# comfort_board.net
KiCad netlist of a schematic drawn in EAGLE
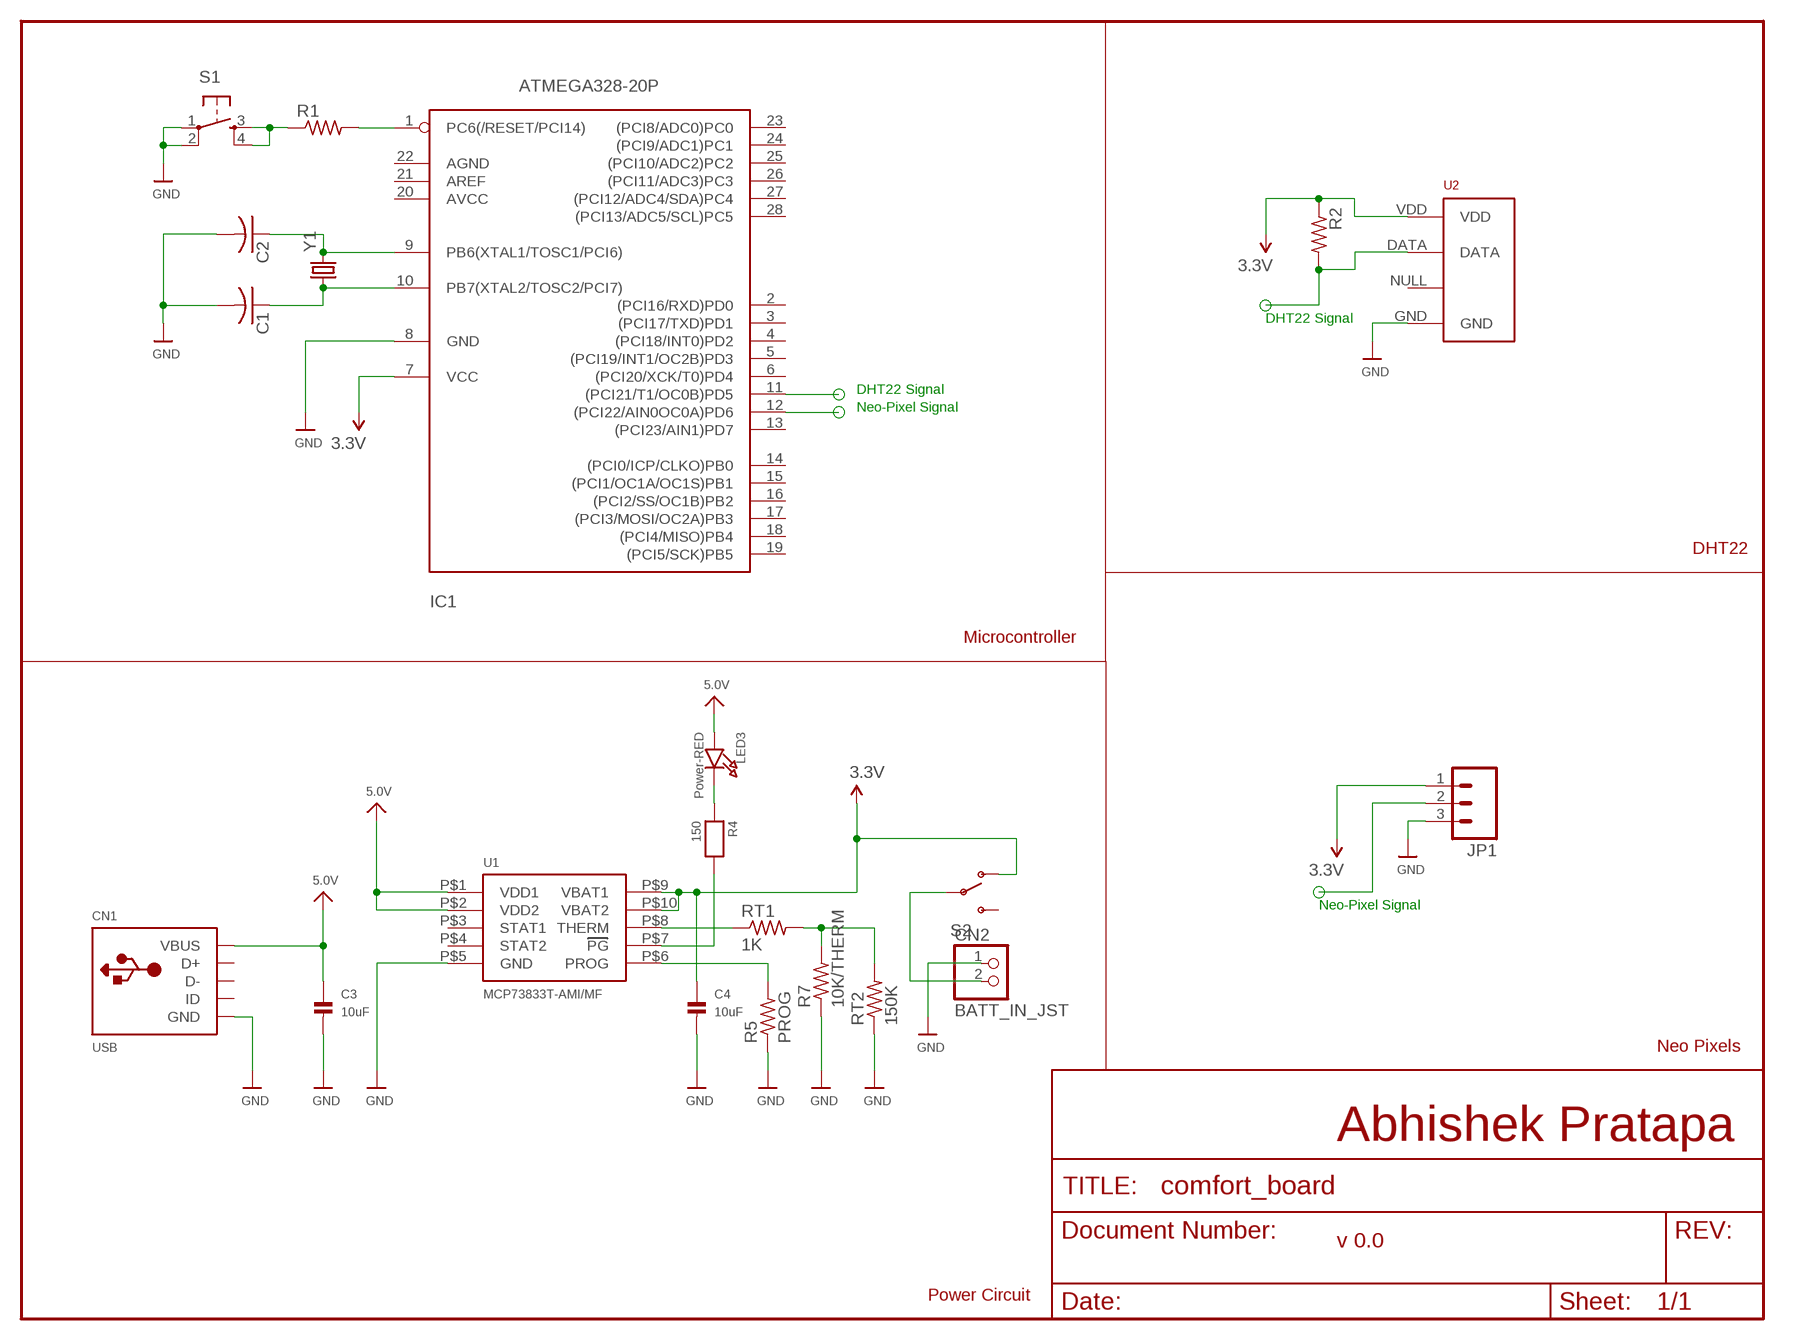
[diagram p0: schematic, sheet 1]

(export (version "E")
  (design (tool "Eeschema 10.0.6"))
  (components
    (comp (ref "C1")
      (value "C-USC1206")
      (footprint "eagle-import:C1206")
      (libsource (lib "eagle-import") (part "C-USC1206"))
    )
    (comp (ref "C2")
      (value "C-USC1206")
      (footprint "eagle-import:C1206")
      (libsource (lib "eagle-import") (part "C-USC1206"))
    )
    (comp (ref "C3")
      (value "10uF")
      (footprint "eagle-import:0805")
      (libsource (lib "eagle-import") (part "CAP_CERAMIC0805"))
    )
    (comp (ref "C4")
      (value "10uF")
      (footprint "eagle-import:0805")
      (libsource (lib "eagle-import") (part "CAP_CERAMIC0805"))
    )
    (comp (ref "CN1")
      (value "USB")
      (footprint "eagle-import:USB-MINIB_LARGER")
      (libsource (lib "eagle-import") (part "USBMINIBLARGE"))
    )
    (comp (ref "CN2")
      (value "BATT_IN_JST")
      (footprint "eagle-import:JSTPH2")
      (libsource (lib "eagle-import") (part "JST_2PIN"))
    )
    (comp (ref "IC1")
      (value "ATMEGA328-20P")
      (footprint "eagle-import:DIL28-3")
      (libsource (lib "eagle-import") (part "ATMEGA328P-20"))
    )
    (comp (ref "JP1")
      (value "M03PTH")
      (footprint "eagle-import:1X03")
      (libsource (lib "eagle-import") (part "M03PTH"))
    )
    (comp (ref "LED3")
      (value "Power-RED")
      (footprint "eagle-import:CHIPLED_0805")
      (libsource (lib "eagle-import") (part "LED0805"))
    )
    (comp (ref "R1")
      (value "R-US_M1206")
      (footprint "eagle-import:M1206")
      (libsource (lib "eagle-import") (part "R-US_M1206"))
    )
    (comp (ref "R2")
      (value "R-US_M1206")
      (footprint "eagle-import:M1206")
      (libsource (lib "eagle-import") (part "resistor_R-US_M1206"))
    )
    (comp (ref "R4")
      (value "150")
      (footprint "eagle-import:0805")
      (libsource (lib "eagle-import") (part "RESISTOR0805"))
    )
    (comp (ref "R5")
      (value "PROG")
      (footprint "eagle-import:0805-THM")
      (libsource (lib "eagle-import") (part "RESISTOR_DUAL"))
    )
    (comp (ref "R7")
      (value "10K/THERM")
      (footprint "eagle-import:0805-THM")
      (libsource (lib "eagle-import") (part "R-US_FLIPFLOP"))
    )
    (comp (ref "RT1")
      (value "1K")
      (footprint "eagle-import:R0805")
      (libsource (lib "eagle-import") (part "R-US_R0805"))
    )
    (comp (ref "RT2")
      (value "150K")
      (footprint "eagle-import:R0805")
      (libsource (lib "eagle-import") (part "R-US_R0805"))
    )
    (comp (ref "S1")
      (value "TAC_SWITCHPTH")
      (footprint "eagle-import:TACTILE-PTH")
      (libsource (lib "eagle-import") (part "TAC_SWITCHPTH"))
    )
    (comp (ref "S2")
      (value "SWITCH-SPSTSMD2")
      (footprint "eagle-import:SWITCH-SPDT-SMD")
      (libsource (lib "eagle-import") (part "SWITCH-SPSTSMD2"))
    )
    (comp (ref "U1")
      (value "MCP73833T-AMI/MF")
      (footprint "eagle-import:DFN10_3X3MM")
      (libsource (lib "eagle-import") (part "MCP73833DFN"))
    )
    (comp (ref "U2")
      (value "RHT03_DHT-22_AM2302RA")
      (footprint "eagle-import:RHT03_DHT-22_RA")
      (libsource (lib "eagle-import") (part "RHT03_DHT-22_AM2302RA"))
    )
    (comp (ref "Y1")
      (value "CRYSTALHC49US")
      (footprint "eagle-import:HC49US")
      (libsource (lib "eagle-import") (part "CRYSTALHC49US"))
    )
  )
  (nets
    (net (code "1") (name "/DHT22") (class "Default")
      (node (ref "IC1") (pin "11") (pinfunction "(PCI21/T1/OC0B)PD5_11") (pintype "bidirectional"))
      (node (ref "R2") (pin "2") (pinfunction "2_2") (pintype "passive"))
      (node (ref "U2") (pin "DATA") (pinfunction "DATA_DATA") (pintype "bidirectional"))
    )
    (net (code "2") (name "/N$6") (class "Default")
      (node (ref "IC1") (pin "12") (pinfunction "(PCI22/AIN0OC0A)PD6_12") (pintype "bidirectional"))
      (node (ref "JP1") (pin "2") (pinfunction "2_2") (pintype "passive"))
    )
    (net (code "3") (name "3.3V") (class "Default")
      (node (ref "C4") (pin "1") (pinfunction "P$1_1") (pintype "passive"))
      (node (ref "IC1") (pin "7") (pinfunction "VCC_7") (pintype "bidirectional"))
      (node (ref "JP1") (pin "1") (pinfunction "1_1") (pintype "passive"))
      (node (ref "R2") (pin "1") (pinfunction "1_1") (pintype "passive"))
      (node (ref "S2") (pin "1") (pinfunction "O_1") (pintype "passive"))
      (node (ref "U1") (pin "P$10") (pinfunction "VBAT2_P$10") (pintype "bidirectional"))
      (node (ref "U1") (pin "P$9") (pinfunction "VBAT1_P$9") (pintype "bidirectional"))
      (node (ref "U2") (pin "VDD") (pinfunction "VDD_VDD") (pintype "power_in"))
    )
    (net (code "4") (name "5.0V") (class "Default")
      (node (ref "C3") (pin "1") (pinfunction "P$1_1") (pintype "passive"))
      (node (ref "CN1") (pin "VBUS") (pinfunction "VBUS_VBUS") (pintype "power_in"))
      (node (ref "LED3") (pin "A") (pinfunction "A_A") (pintype "passive"))
      (node (ref "U1") (pin "P$1") (pinfunction "VDD1_P$1") (pintype "bidirectional"))
      (node (ref "U1") (pin "P$2") (pinfunction "VDD2_P$2") (pintype "bidirectional"))
    )
    (net (code "5") (name "GND") (class "Default")
      (node (ref "C1") (pin "2") (pinfunction "2_2") (pintype "passive"))
      (node (ref "C2") (pin "2") (pinfunction "2_2") (pintype "passive"))
      (node (ref "C3") (pin "2") (pinfunction "P$2_2") (pintype "passive"))
      (node (ref "C4") (pin "2") (pinfunction "P$2_2") (pintype "passive"))
      (node (ref "CN1") (pin "GND") (pinfunction "GND_GND") (pintype "power_in"))
      (node (ref "CN2") (pin "1") (pinfunction "1_1") (pintype "passive"))
      (node (ref "IC1") (pin "8") (pinfunction "GND_8") (pintype "bidirectional"))
      (node (ref "JP1") (pin "3") (pinfunction "3_3") (pintype "passive"))
      (node (ref "R5") (pin "1") (pinfunction "1_1") (pintype "passive"))
      (node (ref "R7") (pin "1") (pinfunction "1_1") (pintype "passive"))
      (node (ref "RT2") (pin "1") (pinfunction "1_1") (pintype "passive"))
      (node (ref "S1") (pin "1") (pinfunction "1_1") (pintype "passive"))
      (node (ref "S1") (pin "2") (pinfunction "2_2") (pintype "passive"))
      (node (ref "U1") (pin "P$5") (pinfunction "GND_P$5") (pintype "bidirectional"))
      (node (ref "U2") (pin "GND") (pinfunction "GND_GND") (pintype "power_in"))
    )
    (net (code "6") (name "Net-(IC1-PB6(XTAL1{slash}TOSC1{slash}PCI6))") (class "Default")
      (node (ref "C2") (pin "1") (pinfunction "1_1") (pintype "passive"))
      (node (ref "IC1") (pin "9") (pinfunction "PB6(XTAL1/TOSC1/PCI6)_9") (pintype "bidirectional"))
      (node (ref "Y1") (pin "2") (pinfunction "2_2") (pintype "passive"))
    )
    (net (code "7") (name "Net-(IC1-PB7(XTAL2{slash}TOSC2{slash}PCI7))") (class "Default")
      (node (ref "C1") (pin "1") (pinfunction "1_1") (pintype "passive"))
      (node (ref "IC1") (pin "10") (pinfunction "PB7(XTAL2/TOSC2/PCI7)_10") (pintype "bidirectional"))
      (node (ref "Y1") (pin "1") (pinfunction "1_1") (pintype "passive"))
    )
    (net (code "8") (name "Net-(IC1-PC6({slash}RESET{slash}PCI14))") (class "Default")
      (node (ref "IC1") (pin "1") (pinfunction "PC6(/RESET/PCI14)_1") (pintype "bidirectional"))
      (node (ref "R1") (pin "2") (pinfunction "2_2") (pintype "passive"))
    )
    (net (code "9") (name "Net-(LED3-PadC)") (class "Default")
      (node (ref "LED3") (pin "C") (pinfunction "C_C") (pintype "passive"))
      (node (ref "R4") (pin "1") (pinfunction "1_1") (pintype "passive"))
    )
    (net (code "10") (name "Net-(R1-Pad1)") (class "Default")
      (node (ref "R1") (pin "1") (pinfunction "1_1") (pintype "passive"))
      (node (ref "S1") (pin "3") (pinfunction "3_3") (pintype "passive"))
      (node (ref "S1") (pin "4") (pinfunction "4_4") (pintype "passive"))
    )
    (net (code "11") (name "Net-(R7-Pad2)") (class "Default")
      (node (ref "R7") (pin "2") (pinfunction "2_2") (pintype "passive"))
      (node (ref "RT1") (pin "2") (pinfunction "2_2") (pintype "passive"))
      (node (ref "RT2") (pin "2") (pinfunction "2_2") (pintype "passive"))
    )
    (net (code "12") (name "Net-(S2-P)") (class "Default")
      (node (ref "CN2") (pin "2") (pinfunction "2_2") (pintype "passive"))
      (node (ref "S2") (pin "2") (pinfunction "P_2") (pintype "passive"))
    )
    (net (code "13") (name "Net-(U1-PG)") (class "Default")
      (node (ref "R4") (pin "2") (pinfunction "2_2") (pintype "passive"))
      (node (ref "U1") (pin "P$7") (pinfunction "PG_P$7") (pintype "bidirectional"))
    )
    (net (code "14") (name "Net-(U1-PROG)") (class "Default")
      (node (ref "R5") (pin "2") (pinfunction "2_2") (pintype "passive"))
      (node (ref "U1") (pin "P$6") (pinfunction "PROG_P$6") (pintype "bidirectional"))
    )
    (net (code "15") (name "Net-(U1-THERM)") (class "Default")
      (node (ref "RT1") (pin "1") (pinfunction "1_1") (pintype "passive"))
      (node (ref "U1") (pin "P$8") (pinfunction "THERM_P$8") (pintype "bidirectional"))
    )
    (net (code "16") (name "unconnected-(CN1-PadD+)") (class "Default")
      (node (ref "CN1") (pin "D+") (pinfunction "D+_D+") (pintype "bidirectional"))
    )
    (net (code "17") (name "unconnected-(CN1-PadD-)") (class "Default")
      (node (ref "CN1") (pin "D-") (pinfunction "D-_D-") (pintype "bidirectional"))
    )
    (net (code "18") (name "unconnected-(CN1-PadID)") (class "Default")
      (node (ref "CN1") (pin "ID") (pinfunction "ID_ID") (pintype "bidirectional"))
    )
    (net (code "19") (name "unconnected-(IC1-(PCI0{slash}ICP{slash}CLKO)PB0-Pad14)") (class "Default")
      (node (ref "IC1") (pin "14") (pinfunction "(PCI0/ICP/CLKO)PB0_14") (pintype "bidirectional"))
    )
    (net (code "20") (name "unconnected-(IC1-(PCI1{slash}OC1A{slash}OC1S)PB1-Pad15)") (class "Default")
      (node (ref "IC1") (pin "15") (pinfunction "(PCI1/OC1A/OC1S)PB1_15") (pintype "bidirectional"))
    )
    (net (code "21") (name "unconnected-(IC1-(PCI2{slash}SS{slash}OC1B)PB2-Pad16)") (class "Default")
      (node (ref "IC1") (pin "16") (pinfunction "(PCI2/SS/OC1B)PB2_16") (pintype "bidirectional"))
    )
    (net (code "22") (name "unconnected-(IC1-(PCI3{slash}MOSI{slash}OC2A)PB3-Pad17)") (class "Default")
      (node (ref "IC1") (pin "17") (pinfunction "(PCI3/MOSI/OC2A)PB3_17") (pintype "bidirectional"))
    )
    (net (code "23") (name "unconnected-(IC1-(PCI4{slash}MISO)PB4-Pad18)") (class "Default")
      (node (ref "IC1") (pin "18") (pinfunction "(PCI4/MISO)PB4_18") (pintype "bidirectional"))
    )
    (net (code "24") (name "unconnected-(IC1-(PCI5{slash}SCK)PB5-Pad19)") (class "Default")
      (node (ref "IC1") (pin "19") (pinfunction "(PCI5/SCK)PB5_19") (pintype "bidirectional"))
    )
    (net (code "25") (name "unconnected-(IC1-(PCI8{slash}ADC0)PC0-Pad23)") (class "Default")
      (node (ref "IC1") (pin "23") (pinfunction "(PCI8/ADC0)PC0_23") (pintype "bidirectional"))
    )
    (net (code "26") (name "unconnected-(IC1-(PCI9{slash}ADC1)PC1-Pad24)") (class "Default")
      (node (ref "IC1") (pin "24") (pinfunction "(PCI9/ADC1)PC1_24") (pintype "bidirectional"))
    )
    (net (code "27") (name "unconnected-(IC1-(PCI10{slash}ADC2)PC2-Pad25)") (class "Default")
      (node (ref "IC1") (pin "25") (pinfunction "(PCI10/ADC2)PC2_25") (pintype "bidirectional"))
    )
    (net (code "28") (name "unconnected-(IC1-(PCI11{slash}ADC3)PC3-Pad26)") (class "Default")
      (node (ref "IC1") (pin "26") (pinfunction "(PCI11/ADC3)PC3_26") (pintype "bidirectional"))
    )
    (net (code "29") (name "unconnected-(IC1-(PCI12{slash}ADC4{slash}SDA)PC4-Pad27)") (class "Default")
      (node (ref "IC1") (pin "27") (pinfunction "(PCI12/ADC4/SDA)PC4_27") (pintype "bidirectional"))
    )
    (net (code "30") (name "unconnected-(IC1-(PCI13{slash}ADC5{slash}SCL)PC5-Pad28)") (class "Default")
      (node (ref "IC1") (pin "28") (pinfunction "(PCI13/ADC5/SCL)PC5_28") (pintype "bidirectional"))
    )
    (net (code "31") (name "unconnected-(IC1-(PCI16{slash}RXD)PD0-Pad2)") (class "Default")
      (node (ref "IC1") (pin "2") (pinfunction "(PCI16/RXD)PD0_2") (pintype "bidirectional"))
    )
    (net (code "32") (name "unconnected-(IC1-(PCI17{slash}TXD)PD1-Pad3)") (class "Default")
      (node (ref "IC1") (pin "3") (pinfunction "(PCI17/TXD)PD1_3") (pintype "bidirectional"))
    )
    (net (code "33") (name "unconnected-(IC1-(PCI18{slash}INT0)PD2-Pad4)") (class "Default")
      (node (ref "IC1") (pin "4") (pinfunction "(PCI18/INT0)PD2_4") (pintype "bidirectional"))
    )
    (net (code "34") (name "unconnected-(IC1-(PCI19{slash}INT1{slash}OC2B)PD3-Pad5)") (class "Default")
      (node (ref "IC1") (pin "5") (pinfunction "(PCI19/INT1/OC2B)PD3_5") (pintype "bidirectional"))
    )
    (net (code "35") (name "unconnected-(IC1-(PCI20{slash}XCK{slash}T0)PD4-Pad6)") (class "Default")
      (node (ref "IC1") (pin "6") (pinfunction "(PCI20/XCK/T0)PD4_6") (pintype "bidirectional"))
    )
    (net (code "36") (name "unconnected-(IC1-(PCI23{slash}AIN1)PD7-Pad13)") (class "Default")
      (node (ref "IC1") (pin "13") (pinfunction "(PCI23/AIN1)PD7_13") (pintype "bidirectional"))
    )
    (net (code "37") (name "unconnected-(IC1-AGND-Pad22)") (class "Default")
      (node (ref "IC1") (pin "22") (pinfunction "AGND_22") (pintype "bidirectional"))
    )
    (net (code "38") (name "unconnected-(IC1-AREF-Pad21)") (class "Default")
      (node (ref "IC1") (pin "21") (pinfunction "AREF_21") (pintype "bidirectional"))
    )
    (net (code "39") (name "unconnected-(IC1-AVCC-Pad20)") (class "Default")
      (node (ref "IC1") (pin "20") (pinfunction "AVCC_20") (pintype "bidirectional"))
    )
    (net (code "40") (name "unconnected-(S2-S-Pad3)") (class "Default")
      (node (ref "S2") (pin "3") (pinfunction "S_3") (pintype "passive"))
    )
    (net (code "41") (name "unconnected-(U1-STAT1-PadP$3)") (class "Default")
      (node (ref "U1") (pin "P$3") (pinfunction "STAT1_P$3") (pintype "bidirectional"))
    )
    (net (code "42") (name "unconnected-(U1-STAT2-PadP$4)") (class "Default")
      (node (ref "U1") (pin "P$4") (pinfunction "STAT2_P$4") (pintype "bidirectional"))
    )
    (net (code "43") (name "unconnected-(U2-PadNULL)") (class "Default")
      (node (ref "U2") (pin "NULL") (pinfunction "NULL_NULL") (pintype "no_connect"))
    )
  )
)
